# Addon-mapleCUx_Raspi-3V3-UART-CC2530-V02.net
KiCad netlist of a schematic drawn in EAGLE
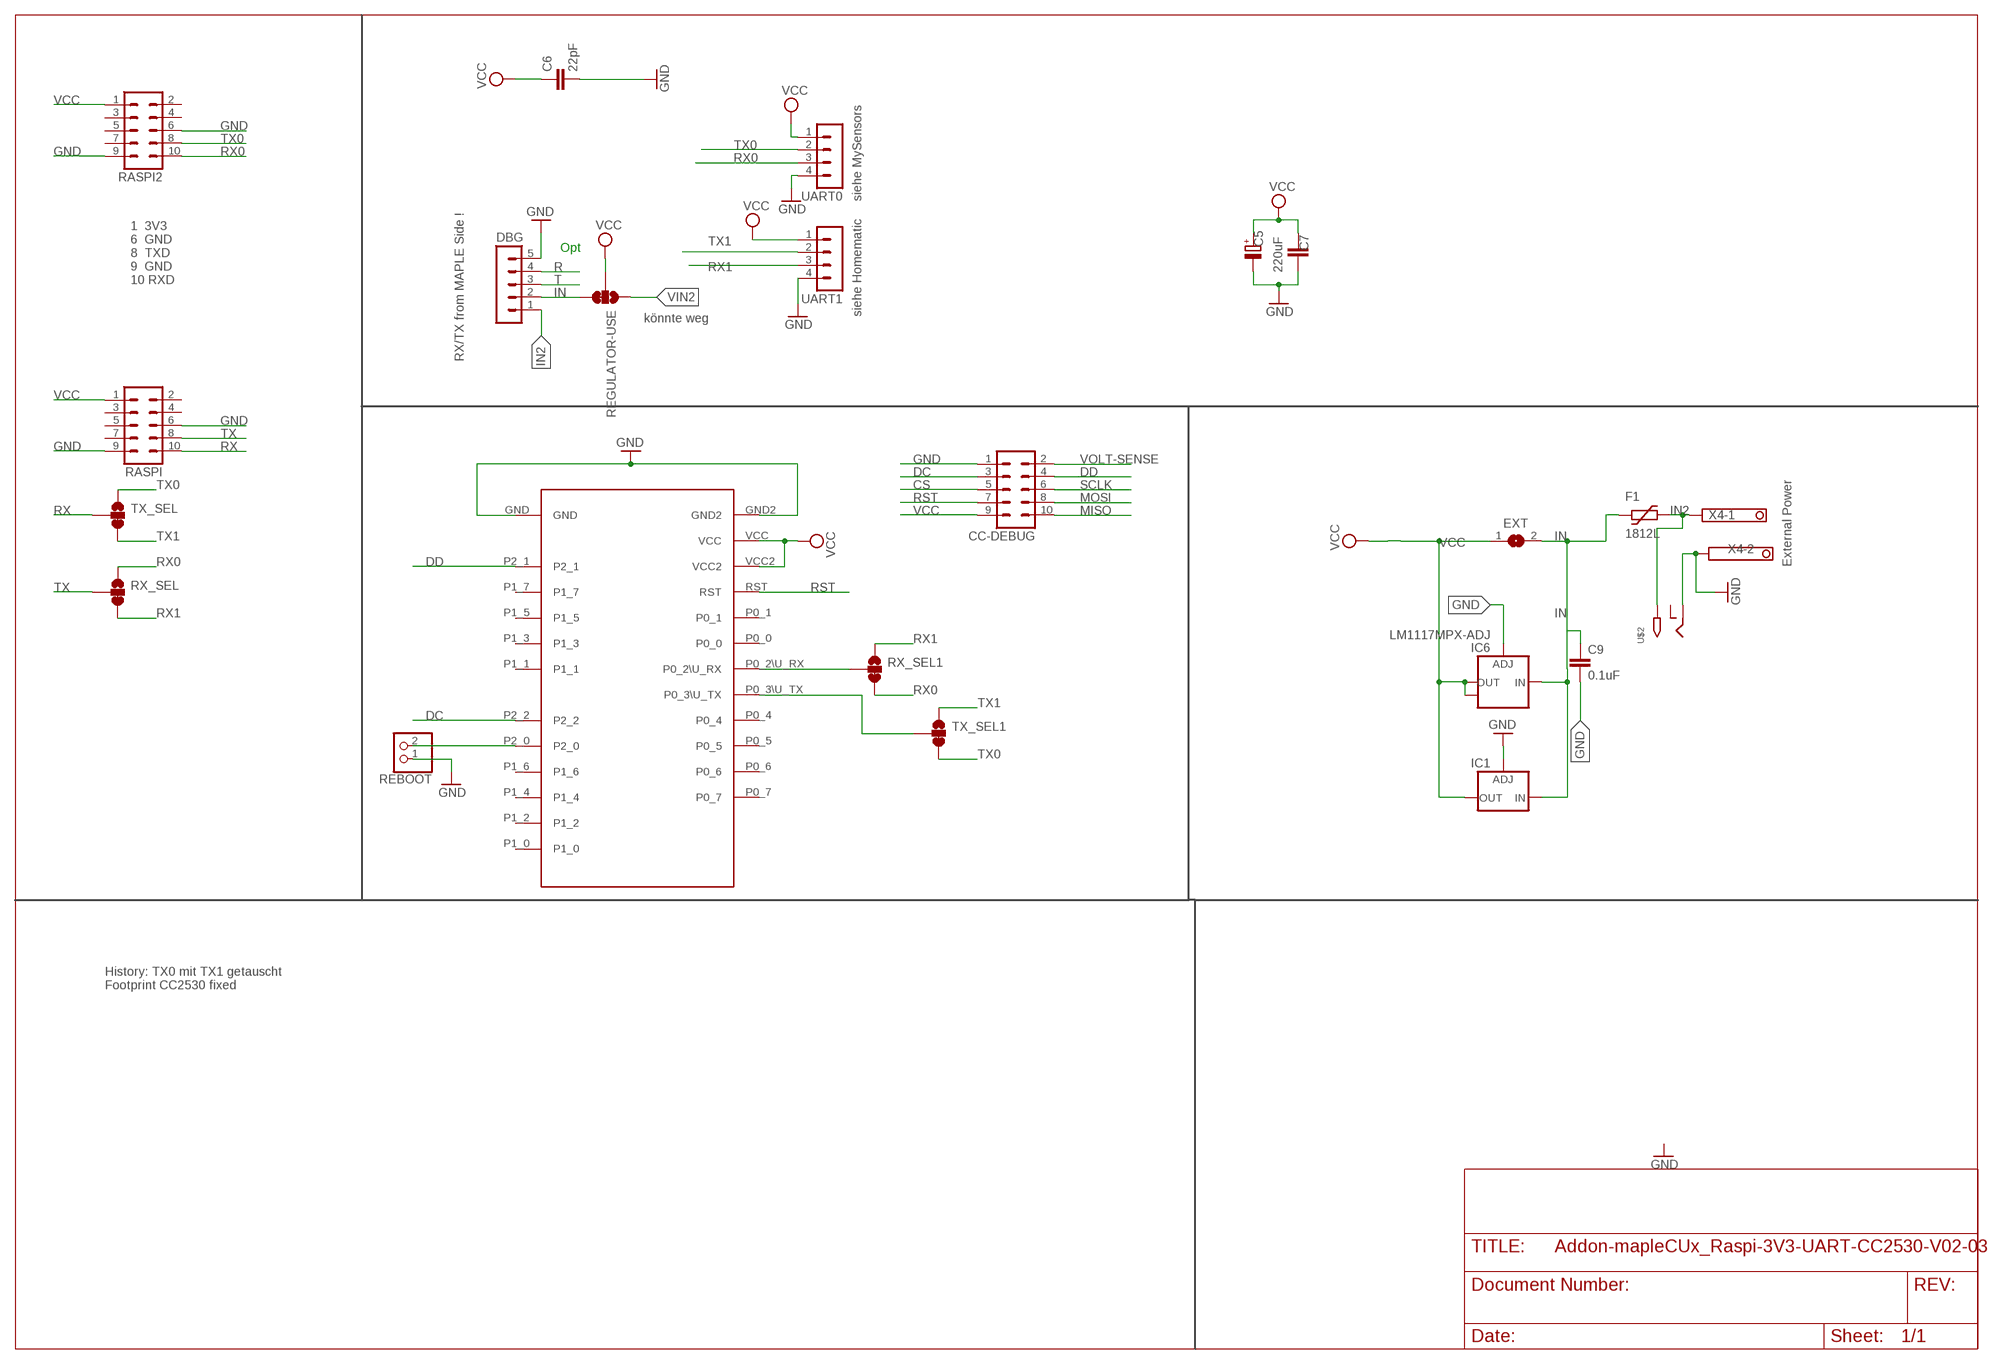
[diagram p0: schematic, sheet 1]

(export (version "E")
  (design (tool "Eeschema 10.0.6"))
  (components
    (comp (ref "C5")
      (value "220uF")
      (footprint "eagle-import:E5-8,5")
      (libsource (lib "eagle-import") (part "CPOL-EUE5-8.5"))
    )
    (comp (ref "C6")
      (value "22pF")
      (footprint "eagle-import:C0805")
      (libsource (lib "eagle-import") (part "C-EUC0805"))
    )
    (comp (ref "C7")
      (value "C-EUC1812")
      (footprint "eagle-import:C1812")
      (libsource (lib "eagle-import") (part "C-EUC1812"))
    )
    (comp (ref "C9")
      (value "0.1uF")
      (footprint "eagle-import:C1206")
      (libsource (lib "eagle-import") (part "C-EUC1206"))
    )
    (comp (ref "CC-DEBUG")
      (value "MA05-2")
      (footprint "eagle-import:MA05-2")
      (libsource (lib "eagle-import") (part "MA05-2"))
    )
    (comp (ref "DBG")
      (value "MA05-1")
      (footprint "eagle-import:MA05-1")
      (libsource (lib "eagle-import") (part "MA05-1"))
    )
    (comp (ref "EXT") (value "SJ") (footprint "eagle-import:SJ") (libsource (lib "eagle-import") (part "SJ")))
    (comp (ref "F1")
      (value "1812L")
      (footprint "eagle-import:1812L")
      (libsource (lib "eagle-import") (part "1812L"))
    )
    (comp (ref "IC1")
      (value "LD117ADT50TR")
      (footprint "eagle-import:DPACK")
      (libsource (lib "eagle-import") (part "LD117A?DT50TR"))
    )
    (comp (ref "IC6")
      (value "LM1117MPX-ADJ")
      (footprint "eagle-import:SOT223")
      (libsource (lib "eagle-import") (part "LM1117MPX-ADJ"))
    )
    (comp (ref "RASPI")
      (value "MA05-2")
      (footprint "eagle-import:MA05-2")
      (libsource (lib "eagle-import") (part "MA05-2"))
    )
    (comp (ref "RASPI2")
      (value "MA05-2")
      (footprint "eagle-import:MA05-2")
      (libsource (lib "eagle-import") (part "MA05-2"))
    )
    (comp (ref "REBOOT")
      (value "PINHD-1X2")
      (footprint "eagle-import:1X02")
      (libsource (lib "eagle-import") (part "PINHD-1X2"))
    )
    (comp (ref "REGULATOR-USE")
      (value "JUMPER-SMT_3_1-NC_TRACE_SILK")
      (footprint "eagle-import:SMT-JUMPER_3_1-NC_TRACE_SILK")
      (libsource (lib "eagle-import") (part "JUMPER-SMT_3_1-NC_TRACE_SILK"))
    )
    (comp (ref "RX_SEL")
      (value "JUMPER-SMT_3_1-NC_TRACE_SILK")
      (footprint "eagle-import:SMT-JUMPER_3_1-NC_TRACE_SILK")
      (libsource (lib "eagle-import") (part "JUMPER-SMT_3_1-NC_TRACE_SILK"))
    )
    (comp (ref "RX_SEL1")
      (value "JUMPER-SMT_3_1-NC_TRACE_SILK")
      (footprint "eagle-import:SMT-JUMPER_3_1-NC_TRACE_SILK")
      (libsource (lib "eagle-import") (part "JUMPER-SMT_3_1-NC_TRACE_SILK"))
    )
    (comp (ref "TX_SEL")
      (value "JUMPER-SMT_3_1-NC_TRACE_SILK")
      (footprint "eagle-import:SMT-JUMPER_3_1-NC_TRACE_SILK")
      (libsource (lib "eagle-import") (part "JUMPER-SMT_3_1-NC_TRACE_SILK"))
    )
    (comp (ref "TX_SEL1")
      (value "JUMPER-SMT_3_1-NC_TRACE_SILK")
      (footprint "eagle-import:SMT-JUMPER_3_1-NC_TRACE_SILK")
      (libsource (lib "eagle-import") (part "JUMPER-SMT_3_1-NC_TRACE_SILK"))
    )
    (comp (ref "U$2")
      (value "2.1MMJACKTHM")
      (footprint "eagle-import:PJ-102A")
      (libsource (lib "eagle-import") (part "2.1MMJACKTHM"))
    )
    (comp (ref "U$3")
      (value "CC2530_MODULE")
      (footprint "eagle-import:CC2530_DIL")
      (libsource (lib "eagle-import") (part "CC2530_MODULE"))
    )
    (comp (ref "UART0")
      (value "MA04-1")
      (footprint "eagle-import:MA04-1")
      (libsource (lib "eagle-import") (part "MA04-1"))
    )
    (comp (ref "UART1")
      (value "MA04-1")
      (footprint "eagle-import:MA04-1")
      (libsource (lib "eagle-import") (part "MA04-1"))
    )
    (comp (ref "X4")
      (value "1751248")
      (footprint "eagle-import:1751248")
      (libsource (lib "eagle-import") (part "1751248"))
    )
  )
  (nets
    (net (code "1") (name "/CS") (class "Default")
      (node (ref "CC-DEBUG") (pin "5") (pinfunction "5_5") (pintype "passive"))
    )
    (net (code "2") (name "/DC") (class "Default")
      (node (ref "CC-DEBUG") (pin "3") (pinfunction "3_3") (pintype "passive"))
      (node (ref "U$3") (pin "P2_2") (pinfunction "P2_2_P2_2") (pintype "bidirectional"))
    )
    (net (code "3") (name "/DD") (class "Default")
      (node (ref "CC-DEBUG") (pin "4") (pinfunction "4_4") (pintype "passive"))
      (node (ref "U$3") (pin "P2_1") (pinfunction "P2_1_P2_1") (pintype "bidirectional"))
    )
    (net (code "4") (name "/IN") (class "Default")
      (node (ref "C9") (pin "1") (pinfunction "1_1") (pintype "passive"))
      (node (ref "DBG") (pin "2") (pinfunction "2_2") (pintype "passive"))
      (node (ref "EXT") (pin "2") (pinfunction "2_2") (pintype "passive"))
      (node (ref "F1") (pin "P$1") (pinfunction "1_P$1") (pintype "passive"))
      (node (ref "IC1") (pin "3") (pinfunction "IN_3") (pintype "input"))
      (node (ref "IC6") (pin "3") (pinfunction "IN_3") (pintype "input"))
      (node (ref "REGULATOR-USE") (pin "3") (pinfunction "3_3") (pintype "passive"))
    )
    (net (code "5") (name "/MISO") (class "Default")
      (node (ref "CC-DEBUG") (pin "10") (pinfunction "10_10") (pintype "passive"))
    )
    (net (code "6") (name "/MOSI") (class "Default")
      (node (ref "CC-DEBUG") (pin "8") (pinfunction "8_8") (pintype "passive"))
    )
    (net (code "7") (name "/R") (class "Default")
      (node (ref "DBG") (pin "4") (pinfunction "4_4") (pintype "passive"))
    )
    (net (code "8") (name "/RST") (class "Default")
      (node (ref "CC-DEBUG") (pin "7") (pinfunction "7_7") (pintype "passive"))
      (node (ref "U$3") (pin "RST") (pinfunction "RST_RST") (pintype "bidirectional"))
    )
    (net (code "9") (name "/RX") (class "Default")
      (node (ref "RASPI") (pin "10") (pinfunction "10_10") (pintype "passive"))
      (node (ref "TX_SEL") (pin "2") (pinfunction "2_2") (pintype "passive"))
    )
    (net (code "10") (name "/RX0") (class "Default")
      (node (ref "RASPI2") (pin "10") (pinfunction "10_10") (pintype "passive"))
      (node (ref "RX_SEL") (pin "1") (pinfunction "1_1") (pintype "passive"))
      (node (ref "RX_SEL1") (pin "3") (pinfunction "3_3") (pintype "passive"))
      (node (ref "UART0") (pin "3") (pinfunction "3_3") (pintype "passive"))
    )
    (net (code "11") (name "/RX1") (class "Default")
      (node (ref "RX_SEL") (pin "3") (pinfunction "3_3") (pintype "passive"))
      (node (ref "RX_SEL1") (pin "1") (pinfunction "1_1") (pintype "passive"))
      (node (ref "UART1") (pin "3") (pinfunction "3_3") (pintype "passive"))
    )
    (net (code "12") (name "/SCLK") (class "Default")
      (node (ref "CC-DEBUG") (pin "6") (pinfunction "6_6") (pintype "passive"))
    )
    (net (code "13") (name "/T") (class "Default")
      (node (ref "DBG") (pin "3") (pinfunction "3_3") (pintype "passive"))
    )
    (net (code "14") (name "/TX") (class "Default")
      (node (ref "RASPI") (pin "8") (pinfunction "8_8") (pintype "passive"))
      (node (ref "RX_SEL") (pin "2") (pinfunction "2_2") (pintype "passive"))
    )
    (net (code "15") (name "/TX0") (class "Default")
      (node (ref "RASPI2") (pin "8") (pinfunction "8_8") (pintype "passive"))
      (node (ref "TX_SEL") (pin "1") (pinfunction "1_1") (pintype "passive"))
      (node (ref "TX_SEL1") (pin "3") (pinfunction "3_3") (pintype "passive"))
      (node (ref "UART0") (pin "2") (pinfunction "2_2") (pintype "passive"))
    )
    (net (code "16") (name "/TX1") (class "Default")
      (node (ref "TX_SEL") (pin "3") (pinfunction "3_3") (pintype "passive"))
      (node (ref "TX_SEL1") (pin "1") (pinfunction "1_1") (pintype "passive"))
      (node (ref "UART1") (pin "2") (pinfunction "2_2") (pintype "passive"))
    )
    (net (code "17") (name "/VOLT-SENSE") (class "Default")
      (node (ref "CC-DEBUG") (pin "2") (pinfunction "2_2") (pintype "passive"))
    )
    (net (code "18") (name "GND") (class "Default")
      (node (ref "C5") (pin "-") (pinfunction "-_-") (pintype "passive"))
      (node (ref "C6") (pin "2") (pinfunction "2_2") (pintype "passive"))
      (node (ref "C7") (pin "1") (pinfunction "1_1") (pintype "passive"))
      (node (ref "C9") (pin "2") (pinfunction "2_2") (pintype "passive"))
      (node (ref "CC-DEBUG") (pin "1") (pinfunction "1_1") (pintype "passive"))
      (node (ref "DBG") (pin "5") (pinfunction "5_5") (pintype "passive"))
      (node (ref "IC1") (pin "1") (pinfunction "ADJ_1") (pintype "input"))
      (node (ref "IC6") (pin "1") (pinfunction "ADJ_1") (pintype "input"))
      (node (ref "RASPI") (pin "6") (pinfunction "6_6") (pintype "passive"))
      (node (ref "RASPI") (pin "9") (pinfunction "9_9") (pintype "passive"))
      (node (ref "RASPI2") (pin "6") (pinfunction "6_6") (pintype "passive"))
      (node (ref "RASPI2") (pin "9") (pinfunction "9_9") (pintype "passive"))
      (node (ref "REBOOT") (pin "1") (pinfunction "1_1") (pintype "passive"))
      (node (ref "U$2") (pin "RING") (pinfunction "RING_RING") (pintype "bidirectional"))
      (node (ref "U$3") (pin "GND") (pinfunction "GND_GND") (pintype "bidirectional"))
      (node (ref "U$3") (pin "GND2") (pinfunction "GND2_GND2") (pintype "bidirectional"))
      (node (ref "UART0") (pin "4") (pinfunction "4_4") (pintype "passive"))
      (node (ref "UART1") (pin "4") (pinfunction "4_4") (pintype "passive"))
      (node (ref "X4") (pin "2") (pinfunction "K_2") (pintype "passive"))
    )
    (net (code "19") (name "IN2") (class "Default")
      (node (ref "DBG") (pin "1") (pinfunction "1_1") (pintype "passive"))
      (node (ref "F1") (pin "P$2") (pinfunction "2_P$2") (pintype "passive"))
      (node (ref "U$2") (pin "TIP") (pinfunction "TIP_TIP") (pintype "bidirectional"))
      (node (ref "X4") (pin "1") (pinfunction "K_1") (pintype "passive"))
    )
    (net (code "20") (name "Net-(REBOOT-Pad2)") (class "Default")
      (node (ref "REBOOT") (pin "2") (pinfunction "2_2") (pintype "passive"))
      (node (ref "U$3") (pin "P2_0") (pinfunction "P2_0_P2_0") (pintype "bidirectional"))
    )
    (net (code "21") (name "Net-(RX_SEL1-Pad2)") (class "Default")
      (node (ref "RX_SEL1") (pin "2") (pinfunction "2_2") (pintype "passive"))
      (node (ref "U$3") (pin "P0_2\\U_RX") (pinfunction "P0_2\\U_RX_P0_2\\U_RX") (pintype "bidirectional"))
    )
    (net (code "22") (name "Net-(TX_SEL1-Pad2)") (class "Default")
      (node (ref "TX_SEL1") (pin "2") (pinfunction "2_2") (pintype "passive"))
      (node (ref "U$3") (pin "P0_3\\U_TX") (pinfunction "P0_3\\U_TX_P0_3\\U_TX") (pintype "bidirectional"))
    )
    (net (code "23") (name "VCC") (class "Default")
      (node (ref "C5") (pin "+") (pinfunction "+_+") (pintype "passive"))
      (node (ref "C6") (pin "1") (pinfunction "1_1") (pintype "passive"))
      (node (ref "C7") (pin "2") (pinfunction "2_2") (pintype "passive"))
      (node (ref "CC-DEBUG") (pin "9") (pinfunction "9_9") (pintype "passive"))
      (node (ref "EXT") (pin "1") (pinfunction "1_1") (pintype "passive"))
      (node (ref "IC1") (pin "4") (pinfunction "OUT_4") (pintype "passive"))
      (node (ref "IC6") (pin "2") (pinfunction "OUT_2") (pintype "passive"))
      (node (ref "IC6") (pin "TAB") (pinfunction "OUT1_TAB") (pintype "passive"))
      (node (ref "RASPI") (pin "1") (pinfunction "1_1") (pintype "passive"))
      (node (ref "RASPI2") (pin "1") (pinfunction "1_1") (pintype "passive"))
      (node (ref "REGULATOR-USE") (pin "2") (pinfunction "2_2") (pintype "passive"))
      (node (ref "U$3") (pin "VCC") (pinfunction "VCC_VCC") (pintype "bidirectional"))
      (node (ref "U$3") (pin "VCC2") (pinfunction "VCC2_VCC2") (pintype "bidirectional"))
      (node (ref "UART0") (pin "1") (pinfunction "1_1") (pintype "passive"))
      (node (ref "UART1") (pin "1") (pinfunction "1_1") (pintype "passive"))
    )
    (net (code "24") (name "VIN2") (class "Default")
      (node (ref "REGULATOR-USE") (pin "1") (pinfunction "1_1") (pintype "passive"))
    )
    (net (code "25") (name "unconnected-(RASPI-Pad2)") (class "Default")
      (node (ref "RASPI") (pin "2") (pinfunction "2_2") (pintype "passive"))
    )
    (net (code "26") (name "unconnected-(RASPI-Pad3)") (class "Default")
      (node (ref "RASPI") (pin "3") (pinfunction "3_3") (pintype "passive"))
    )
    (net (code "27") (name "unconnected-(RASPI-Pad4)") (class "Default")
      (node (ref "RASPI") (pin "4") (pinfunction "4_4") (pintype "passive"))
    )
    (net (code "28") (name "unconnected-(RASPI-Pad5)") (class "Default")
      (node (ref "RASPI") (pin "5") (pinfunction "5_5") (pintype "passive"))
    )
    (net (code "29") (name "unconnected-(RASPI-Pad7)") (class "Default")
      (node (ref "RASPI") (pin "7") (pinfunction "7_7") (pintype "passive"))
    )
    (net (code "30") (name "unconnected-(RASPI2-Pad2)") (class "Default")
      (node (ref "RASPI2") (pin "2") (pinfunction "2_2") (pintype "passive"))
    )
    (net (code "31") (name "unconnected-(RASPI2-Pad3)") (class "Default")
      (node (ref "RASPI2") (pin "3") (pinfunction "3_3") (pintype "passive"))
    )
    (net (code "32") (name "unconnected-(RASPI2-Pad4)") (class "Default")
      (node (ref "RASPI2") (pin "4") (pinfunction "4_4") (pintype "passive"))
    )
    (net (code "33") (name "unconnected-(RASPI2-Pad5)") (class "Default")
      (node (ref "RASPI2") (pin "5") (pinfunction "5_5") (pintype "passive"))
    )
    (net (code "34") (name "unconnected-(RASPI2-Pad7)") (class "Default")
      (node (ref "RASPI2") (pin "7") (pinfunction "7_7") (pintype "passive"))
    )
    (net (code "35") (name "unconnected-(U$2-PadRING_SW)") (class "Default")
      (node (ref "U$2") (pin "RING_SW") (pinfunction "RING_SW_RING_SW") (pintype "bidirectional"))
    )
    (net (code "36") (name "unconnected-(U$3-PadP0_0)") (class "Default")
      (node (ref "U$3") (pin "P0_0") (pinfunction "P0_0_P0_0") (pintype "bidirectional"))
    )
    (net (code "37") (name "unconnected-(U$3-PadP0_1)") (class "Default")
      (node (ref "U$3") (pin "P0_1") (pinfunction "P0_1_P0_1") (pintype "bidirectional"))
    )
    (net (code "38") (name "unconnected-(U$3-PadP0_4)") (class "Default")
      (node (ref "U$3") (pin "P0_4") (pinfunction "P0_4_P0_4") (pintype "bidirectional"))
    )
    (net (code "39") (name "unconnected-(U$3-PadP0_5)") (class "Default")
      (node (ref "U$3") (pin "P0_5") (pinfunction "P0_5_P0_5") (pintype "bidirectional"))
    )
    (net (code "40") (name "unconnected-(U$3-PadP0_6)") (class "Default")
      (node (ref "U$3") (pin "P0_6") (pinfunction "P0_6_P0_6") (pintype "bidirectional"))
    )
    (net (code "41") (name "unconnected-(U$3-PadP0_7)") (class "Default")
      (node (ref "U$3") (pin "P0_7") (pinfunction "P0_7_P0_7") (pintype "bidirectional"))
    )
    (net (code "42") (name "unconnected-(U$3-PadP1_0)") (class "Default")
      (node (ref "U$3") (pin "P1_0") (pinfunction "P1_0_P1_0") (pintype "bidirectional"))
    )
    (net (code "43") (name "unconnected-(U$3-PadP1_1)") (class "Default")
      (node (ref "U$3") (pin "P1_1") (pinfunction "P1_1_P1_1") (pintype "bidirectional"))
    )
    (net (code "44") (name "unconnected-(U$3-PadP1_2)") (class "Default")
      (node (ref "U$3") (pin "P1_2") (pinfunction "P1_2_P1_2") (pintype "bidirectional"))
    )
    (net (code "45") (name "unconnected-(U$3-PadP1_3)") (class "Default")
      (node (ref "U$3") (pin "P1_3") (pinfunction "P1_3_P1_3") (pintype "bidirectional"))
    )
    (net (code "46") (name "unconnected-(U$3-PadP1_4)") (class "Default")
      (node (ref "U$3") (pin "P1_4") (pinfunction "P1_4_P1_4") (pintype "bidirectional"))
    )
    (net (code "47") (name "unconnected-(U$3-PadP1_5)") (class "Default")
      (node (ref "U$3") (pin "P1_5") (pinfunction "P1_5_P1_5") (pintype "bidirectional"))
    )
    (net (code "48") (name "unconnected-(U$3-PadP1_6)") (class "Default")
      (node (ref "U$3") (pin "P1_6") (pinfunction "P1_6_P1_6") (pintype "bidirectional"))
    )
    (net (code "49") (name "unconnected-(U$3-PadP1_7)") (class "Default")
      (node (ref "U$3") (pin "P1_7") (pinfunction "P1_7_P1_7") (pintype "bidirectional"))
    )
  )
)
